# Sheet1.net
KiCad netlist of a schematic drawn in Altium Designer
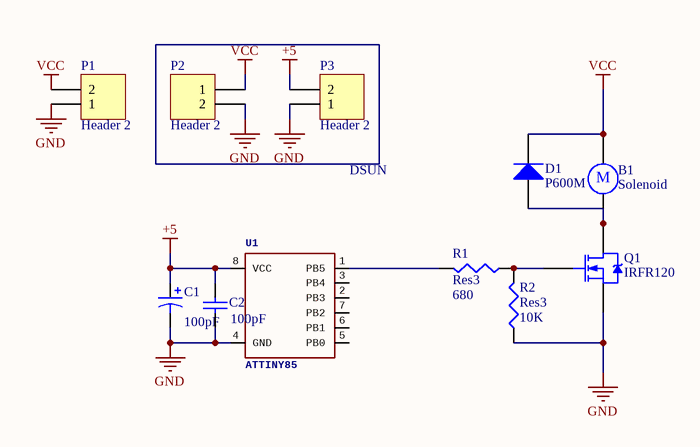
[diagram p0: Sheet1.SchDoc]

(export (version "E")
  (design (tool "Eeschema 10.0.6"))
  (components
    (comp (ref "B1")
      (value "Solenoid")
      (footprint "RB5-10.5")
      (description "Motor, General Kind")
      (fields (field (name "PUBLISHER") "Altium Limited"))
      (libsource (lib "Miscellaneous Devices") (part "Motor"))
    )
    (comp (ref "C1")
      (value "100pF")
      (footprint "C0805")
      (description "Polarized Capacitor (Surface Mount)")
      (fields (field (name "PUBLISHER") "Altium Limited"))
      (libsource (lib "Miscellaneous Devices") (part "Cap Pol3"))
    )
    (comp (ref "C2")
      (value "100pF")
      (footprint "C1206")
      (description "Capacitor (Semiconductor SIM Model)")
      (fields (field (name "PUBLISHER") "Altium Limited"))
      (libsource (lib "Miscellaneous Devices") (part "Cap Semi"))
    )
    (comp (ref "D1")
      (value "P600M")
      (footprint "SMC")
      (description "Default Diode")
      (fields (field (name "PUBLISHER") "Altium Limited"))
      (libsource (lib "Miscellaneous Devices") (part "Diode"))
    )
    (comp (ref "P1")
      (value "Header 2")
      (footprint "HDR1X2")
      (description "Header, 2-Pin")
      (fields (field (name "PUBLISHER") "Altium Limited"))
      (libsource (lib "") (part "Header 2_1"))
    )
    (comp (ref "P2")
      (value "Header 2")
      (footprint "HDR1X2")
      (description "Header, 2-Pin")
      (fields (field (name "PUBLISHER") "Altium Limited"))
      (libsource (lib "Miscellaneous Connectors") (part "Header 2"))
    )
    (comp (ref "P3")
      (value "Header 2")
      (footprint "HDR1X2")
      (description "Header, 2-Pin")
      (fields (field (name "PUBLISHER") "Altium Limited"))
      (libsource (lib "") (part "Header 2_1"))
    )
    (comp (ref "Q1")
      (value "IRFR120")
      (footprint "TO-220AB")
      (description "N-Channel Power MOSFET")
      (fields (field (name "PUBLISHER") "Altium Limited"))
      (libsource (lib "Miscellaneous Devices") (part "NMOS-2"))
    )
    (comp (ref "R1")
      (value "Res3")
      (footprint "14-1210")
      (description "Resistor")
      (fields (field (name "ALTIUM_VALUE") "680") (field (name "PUBLISHER") "Altium Limited"))
      (libsource (lib "Miscellaneous Devices") (part "Res3"))
    )
    (comp (ref "R2")
      (value "Res3")
      (footprint "14-1210")
      (description "Resistor")
      (fields (field (name "ALTIUM_VALUE") "10K") (field (name "PUBLISHER") "Altium Limited"))
      (libsource (lib "Miscellaneous Devices") (part "Res3"))
    )
    (comp (ref "U1")
      (value "ATTINY85")
      (footprint "ATTINY85")
      (libsource (lib "SparkFun-IC-Microcontroller") (part "ATTINY85"))
    )
  )
  (nets
    (net (code "1") (name "+5") (class "Default")
      (node (ref "C1") (pin "1") (pinfunction "1_1") (pintype "passive"))
      (node (ref "C2") (pin "1") (pinfunction "1_1") (pintype "passive"))
      (node (ref "P3") (pin "2") (pinfunction "2_2") (pintype "passive"))
      (node (ref "U1") (pin "8") (pinfunction "VCC_8") (pintype "passive"))
    )
    (net (code "2") (name "GND") (class "Default")
      (node (ref "C1") (pin "2") (pinfunction "2_2") (pintype "passive"))
      (node (ref "C2") (pin "2") (pinfunction "2_2") (pintype "passive"))
      (node (ref "P1") (pin "1") (pinfunction "1_1") (pintype "passive"))
      (node (ref "P2") (pin "2") (pinfunction "2_2") (pintype "passive"))
      (node (ref "P3") (pin "1") (pinfunction "1_1") (pintype "passive"))
      (node (ref "Q1") (pin "3") (pinfunction "S_3") (pintype "passive"))
      (node (ref "R2") (pin "1") (pinfunction "1_1") (pintype "passive"))
      (node (ref "U1") (pin "4") (pinfunction "GND_4") (pintype "passive"))
    )
    (net (code "3") (name "Net-(D1-A)") (class "Default")
      (node (ref "B1") (pin "2") (pinfunction "2_2") (pintype "passive"))
      (node (ref "D1") (pin "1") (pinfunction "A_1") (pintype "passive"))
      (node (ref "Q1") (pin "2") (pinfunction "D_2") (pintype "passive"))
    )
    (net (code "4") (name "Net-(Q1-G)") (class "Default")
      (node (ref "Q1") (pin "1") (pinfunction "G_1") (pintype "passive"))
      (node (ref "R1") (pin "1") (pinfunction "1_1") (pintype "passive"))
      (node (ref "R2") (pin "2") (pinfunction "2_2") (pintype "passive"))
    )
    (net (code "5") (name "Net-(U1-PB5)") (class "Default")
      (node (ref "R1") (pin "2") (pinfunction "2_2") (pintype "passive"))
      (node (ref "U1") (pin "1") (pinfunction "PB5_1") (pintype "passive"))
    )
    (net (code "6") (name "VCC") (class "Default")
      (node (ref "B1") (pin "1") (pinfunction "1_1") (pintype "passive"))
      (node (ref "D1") (pin "2") (pinfunction "K_2") (pintype "passive"))
      (node (ref "P1") (pin "2") (pinfunction "2_2") (pintype "passive"))
      (node (ref "P2") (pin "1") (pinfunction "1_1") (pintype "passive"))
    )
    (net (code "7") (name "unconnected-(U1-PB0-Pad5)") (class "Default")
      (node (ref "U1") (pin "5") (pinfunction "PB0_5") (pintype "passive"))
    )
    (net (code "8") (name "unconnected-(U1-PB1-Pad6)") (class "Default")
      (node (ref "U1") (pin "6") (pinfunction "PB1_6") (pintype "passive"))
    )
    (net (code "9") (name "unconnected-(U1-PB2-Pad7)") (class "Default")
      (node (ref "U1") (pin "7") (pinfunction "PB2_7") (pintype "passive"))
    )
    (net (code "10") (name "unconnected-(U1-PB3-Pad2)") (class "Default")
      (node (ref "U1") (pin "2") (pinfunction "PB3_2") (pintype "passive"))
    )
    (net (code "11") (name "unconnected-(U1-PB4-Pad3)") (class "Default")
      (node (ref "U1") (pin "3") (pinfunction "PB4_3") (pintype "passive"))
    )
  )
)
